# PuenteH.net
KiCad netlist of a schematic drawn in EAGLE
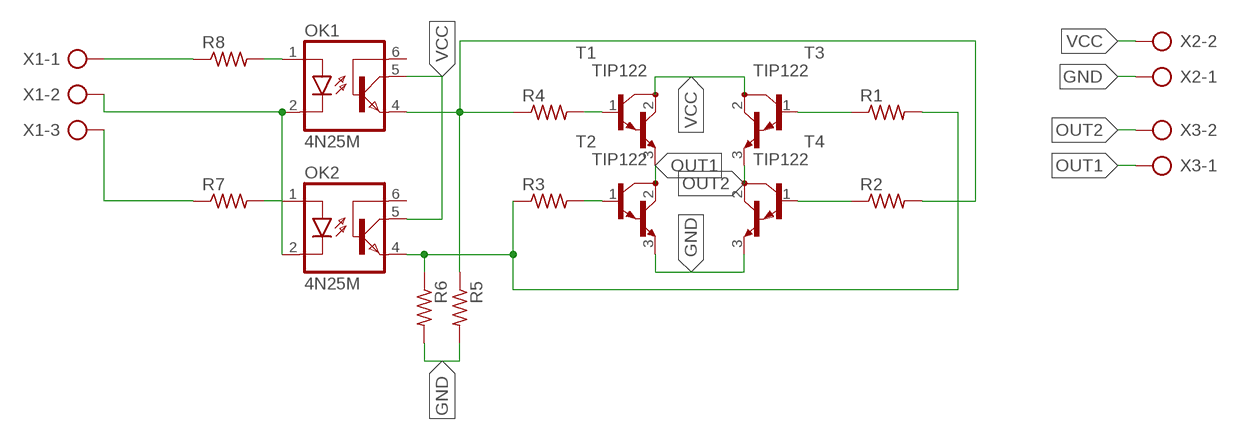
[diagram p0: schematic, sheet 1]

(export (version "E")
  (design (tool "Eeschema 10.0.6"))
  (components
    (comp (ref "OK1")
      (value "4N25M")
      (footprint "eagle-import:DIL06")
      (fields (field (name "MPN") "4N25-M"))
      (libsource (lib "eagle-import") (part "4N?M25"))
    )
    (comp (ref "OK2")
      (value "4N25M")
      (footprint "eagle-import:DIL06")
      (fields (field (name "MPN") "4N25-M"))
      (libsource (lib "eagle-import") (part "4N?M25"))
    )
    (comp (ref "R1")
      (value "R-US_0207/12")
      (footprint "eagle-import:0207_12")
      (libsource (lib "eagle-import") (part "R-US_0207/12"))
    )
    (comp (ref "R2")
      (value "R-US_0207/12")
      (footprint "eagle-import:0207_12")
      (libsource (lib "eagle-import") (part "R-US_0207/12"))
    )
    (comp (ref "R3")
      (value "R-US_0207/12")
      (footprint "eagle-import:0207_12")
      (libsource (lib "eagle-import") (part "R-US_0207/12"))
    )
    (comp (ref "R4")
      (value "R-US_0207/12")
      (footprint "eagle-import:0207_12")
      (libsource (lib "eagle-import") (part "R-US_0207/12"))
    )
    (comp (ref "R5")
      (value "R-US_0207/12")
      (footprint "eagle-import:0207_12")
      (libsource (lib "eagle-import") (part "R-US_0207/12"))
    )
    (comp (ref "R6")
      (value "R-US_0207/12")
      (footprint "eagle-import:0207_12")
      (libsource (lib "eagle-import") (part "R-US_0207/12"))
    )
    (comp (ref "R7")
      (value "R-US_0207/12")
      (footprint "eagle-import:0207_12")
      (libsource (lib "eagle-import") (part "R-US_0207/12"))
    )
    (comp (ref "R8")
      (value "R-US_0207/12")
      (footprint "eagle-import:0207_12")
      (libsource (lib "eagle-import") (part "R-US_0207/12"))
    )
    (comp (ref "T1")
      (value "TIP122")
      (footprint "eagle-import:TO220")
      (libsource (lib "eagle-import") (part "TIP122"))
    )
    (comp (ref "T2")
      (value "TIP122")
      (footprint "eagle-import:TO220")
      (libsource (lib "eagle-import") (part "TIP122"))
    )
    (comp (ref "T3")
      (value "TIP122")
      (footprint "eagle-import:TO220")
      (libsource (lib "eagle-import") (part "TIP122"))
    )
    (comp (ref "T4")
      (value "TIP122")
      (footprint "eagle-import:TO220")
      (libsource (lib "eagle-import") (part "TIP122"))
    )
    (comp (ref "X1")
      (value "AK500/3-H")
      (footprint "eagle-import:AK500_3-H")
      (libsource (lib "eagle-import") (part "AK500/3-H"))
    )
    (comp (ref "X2")
      (value "AK500/2-H")
      (footprint "eagle-import:AK500_2-H")
      (libsource (lib "eagle-import") (part "AK500/2-H"))
    )
    (comp (ref "X3")
      (value "AK500/2-H")
      (footprint "eagle-import:AK500_2-H")
      (libsource (lib "eagle-import") (part "AK500/2-H"))
    )
  )
  (nets
    (net (code "1") (name "GND") (class "Default")
      (node (ref "R5") (pin "2") (pinfunction "2_2") (pintype "passive"))
      (node (ref "R6") (pin "2") (pinfunction "2_2") (pintype "passive"))
      (node (ref "T2") (pin "3") (pinfunction "E_3") (pintype "passive"))
      (node (ref "T4") (pin "3") (pinfunction "E_3") (pintype "passive"))
      (node (ref "X2") (pin "1") (pinfunction "KL_1") (pintype "passive"))
    )
    (net (code "2") (name "Net-(OK1-A)") (class "Default")
      (node (ref "OK1") (pin "1") (pinfunction "A_1") (pintype "passive"))
      (node (ref "R8") (pin "2") (pinfunction "2_2") (pintype "passive"))
    )
    (net (code "3") (name "Net-(OK1-C)") (class "Default")
      (node (ref "OK1") (pin "2") (pinfunction "C_2") (pintype "passive"))
      (node (ref "OK2") (pin "2") (pinfunction "C_2") (pintype "passive"))
      (node (ref "X1") (pin "2") (pinfunction "KL_2") (pintype "passive"))
    )
    (net (code "4") (name "Net-(OK1-EMI)") (class "Default")
      (node (ref "OK1") (pin "4") (pinfunction "EMI_4") (pintype "passive"))
      (node (ref "R2") (pin "2") (pinfunction "2_2") (pintype "passive"))
      (node (ref "R4") (pin "1") (pinfunction "1_1") (pintype "passive"))
      (node (ref "R5") (pin "1") (pinfunction "1_1") (pintype "passive"))
    )
    (net (code "5") (name "Net-(OK2-A)") (class "Default")
      (node (ref "OK2") (pin "1") (pinfunction "A_1") (pintype "passive"))
      (node (ref "R7") (pin "2") (pinfunction "2_2") (pintype "passive"))
    )
    (net (code "6") (name "Net-(OK2-EMI)") (class "Default")
      (node (ref "OK2") (pin "4") (pinfunction "EMI_4") (pintype "passive"))
      (node (ref "R1") (pin "2") (pinfunction "2_2") (pintype "passive"))
      (node (ref "R3") (pin "1") (pinfunction "1_1") (pintype "passive"))
      (node (ref "R6") (pin "1") (pinfunction "1_1") (pintype "passive"))
    )
    (net (code "7") (name "Net-(T1-B)") (class "Default")
      (node (ref "R4") (pin "2") (pinfunction "2_2") (pintype "passive"))
      (node (ref "T1") (pin "1") (pinfunction "B_1") (pintype "passive"))
    )
    (net (code "8") (name "Net-(T2-B)") (class "Default")
      (node (ref "R3") (pin "2") (pinfunction "2_2") (pintype "passive"))
      (node (ref "T2") (pin "1") (pinfunction "B_1") (pintype "passive"))
    )
    (net (code "9") (name "Net-(T3-B)") (class "Default")
      (node (ref "R1") (pin "1") (pinfunction "1_1") (pintype "passive"))
      (node (ref "T3") (pin "1") (pinfunction "B_1") (pintype "passive"))
    )
    (net (code "10") (name "Net-(T4-B)") (class "Default")
      (node (ref "R2") (pin "1") (pinfunction "1_1") (pintype "passive"))
      (node (ref "T4") (pin "1") (pinfunction "B_1") (pintype "passive"))
    )
    (net (code "11") (name "Net-(X1A-KL)") (class "Default")
      (node (ref "R8") (pin "1") (pinfunction "1_1") (pintype "passive"))
      (node (ref "X1") (pin "1") (pinfunction "KL_1") (pintype "passive"))
    )
    (net (code "12") (name "Net-(X1C-KL)") (class "Default")
      (node (ref "R7") (pin "1") (pinfunction "1_1") (pintype "passive"))
      (node (ref "X1") (pin "3") (pinfunction "KL_3") (pintype "passive"))
    )
    (net (code "13") (name "OUT1") (class "Default")
      (node (ref "T1") (pin "3") (pinfunction "E_3") (pintype "passive"))
      (node (ref "T2") (pin "2") (pinfunction "C_2") (pintype "passive"))
      (node (ref "X3") (pin "1") (pinfunction "KL_1") (pintype "passive"))
    )
    (net (code "14") (name "OUT2") (class "Default")
      (node (ref "T3") (pin "3") (pinfunction "E_3") (pintype "passive"))
      (node (ref "T4") (pin "2") (pinfunction "C_2") (pintype "passive"))
      (node (ref "X3") (pin "2") (pinfunction "KL_2") (pintype "passive"))
    )
    (net (code "15") (name "VCC") (class "Default")
      (node (ref "OK1") (pin "5") (pinfunction "COL_5") (pintype "passive"))
      (node (ref "OK2") (pin "5") (pinfunction "COL_5") (pintype "passive"))
      (node (ref "T1") (pin "2") (pinfunction "C_2") (pintype "passive"))
      (node (ref "T3") (pin "2") (pinfunction "C_2") (pintype "passive"))
      (node (ref "X2") (pin "2") (pinfunction "KL_2") (pintype "passive"))
    )
    (net (code "16") (name "unconnected-(OK1-BAS-Pad6)") (class "Default")
      (node (ref "OK1") (pin "6") (pinfunction "BAS_6") (pintype "passive"))
    )
    (net (code "17") (name "unconnected-(OK2-BAS-Pad6)") (class "Default")
      (node (ref "OK2") (pin "6") (pinfunction "BAS_6") (pintype "passive"))
    )
  )
)
